# ModuleCarrier-RAK811-v1_0_0.net
KiCad netlist of a schematic drawn in EAGLE
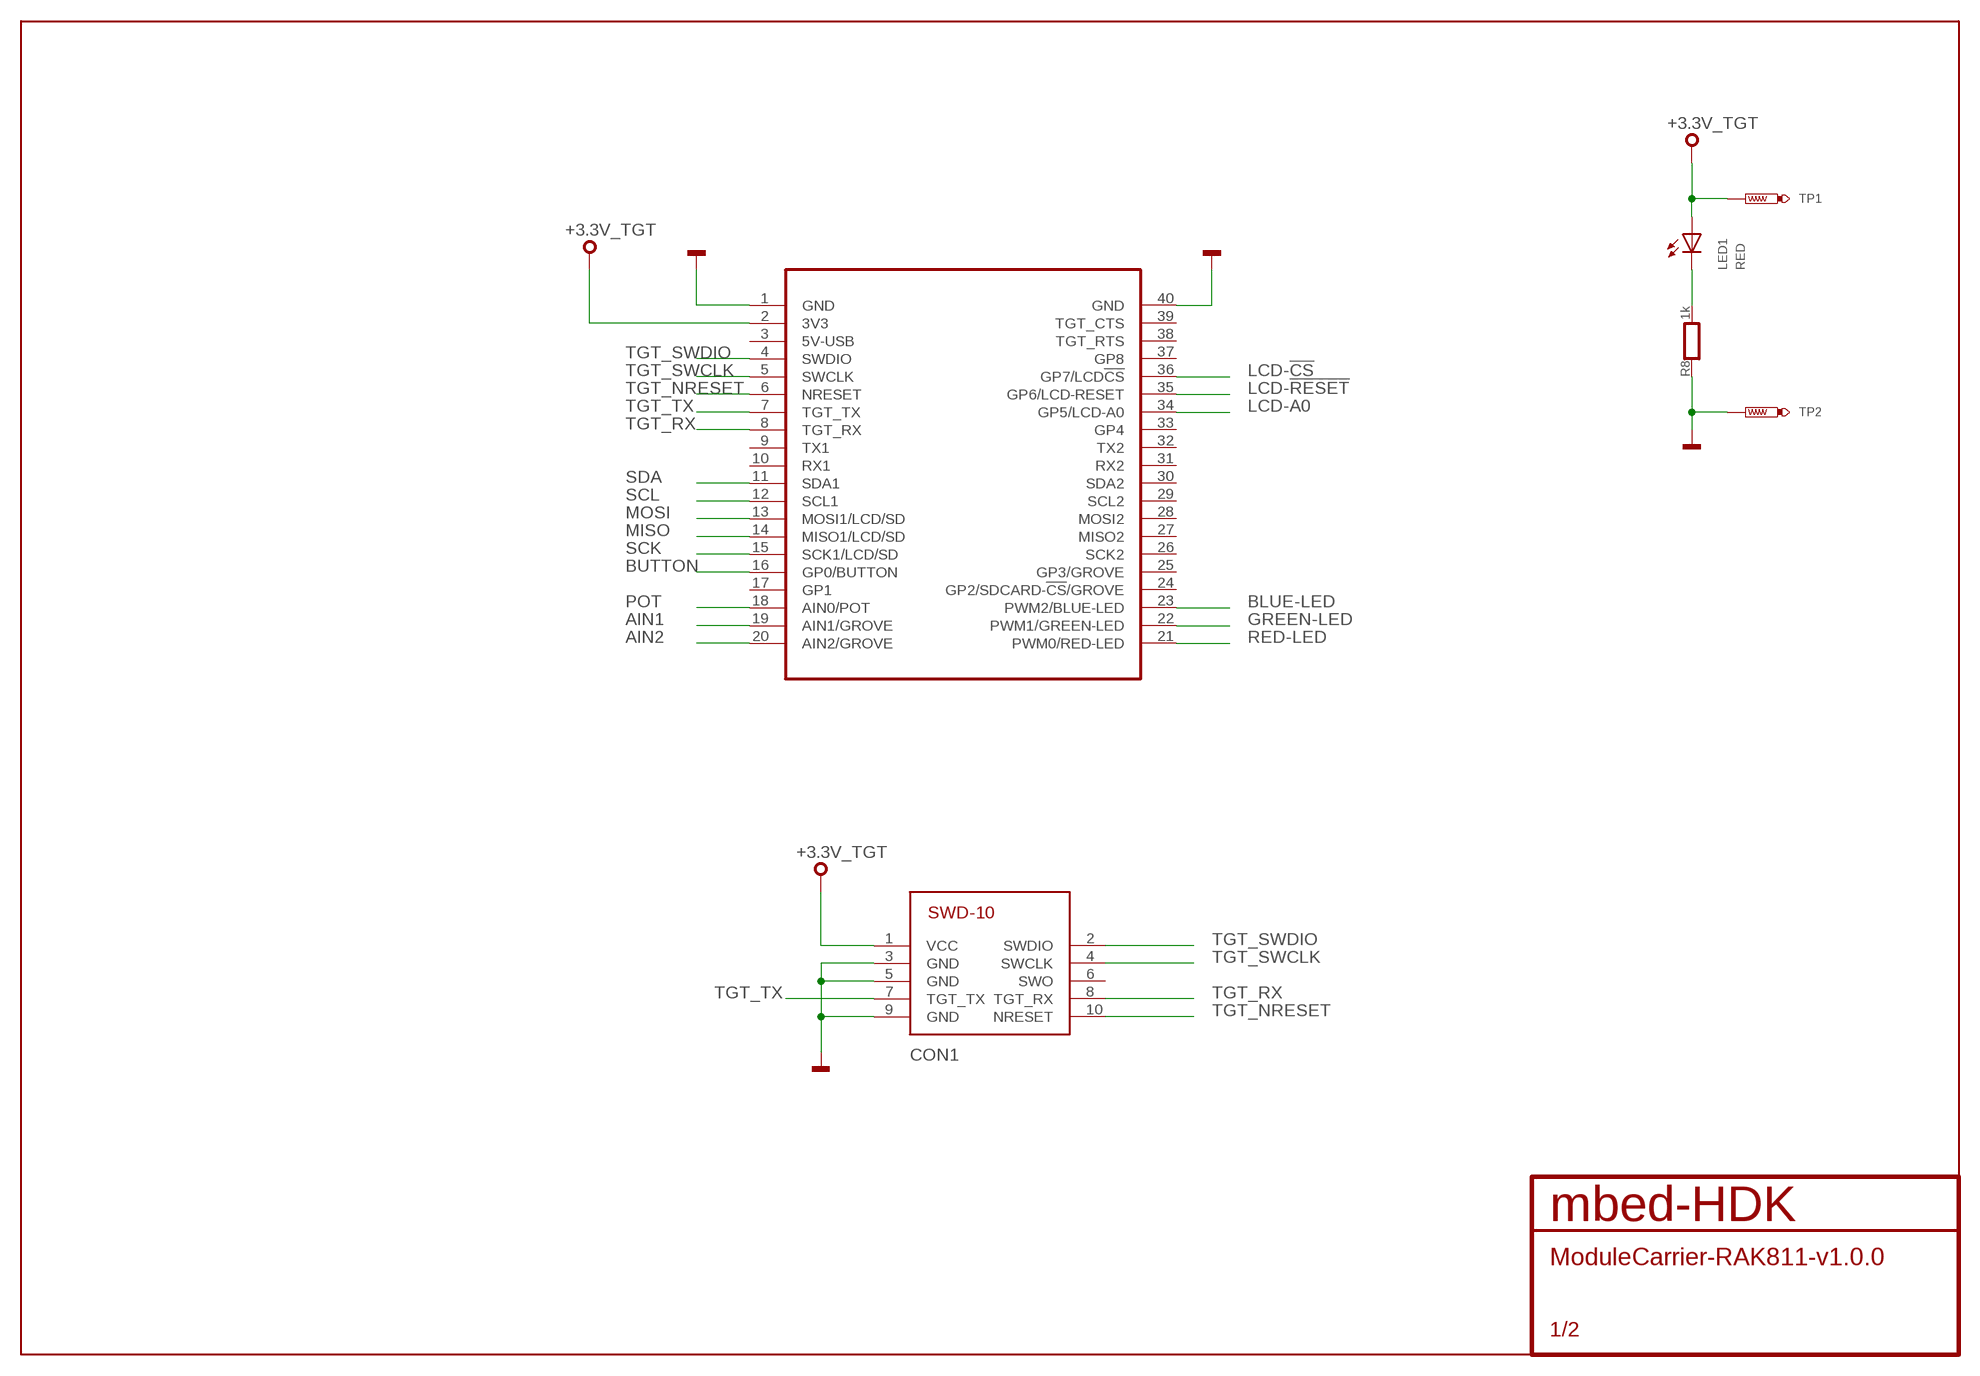
[diagram p0: schematic, sheet 1]
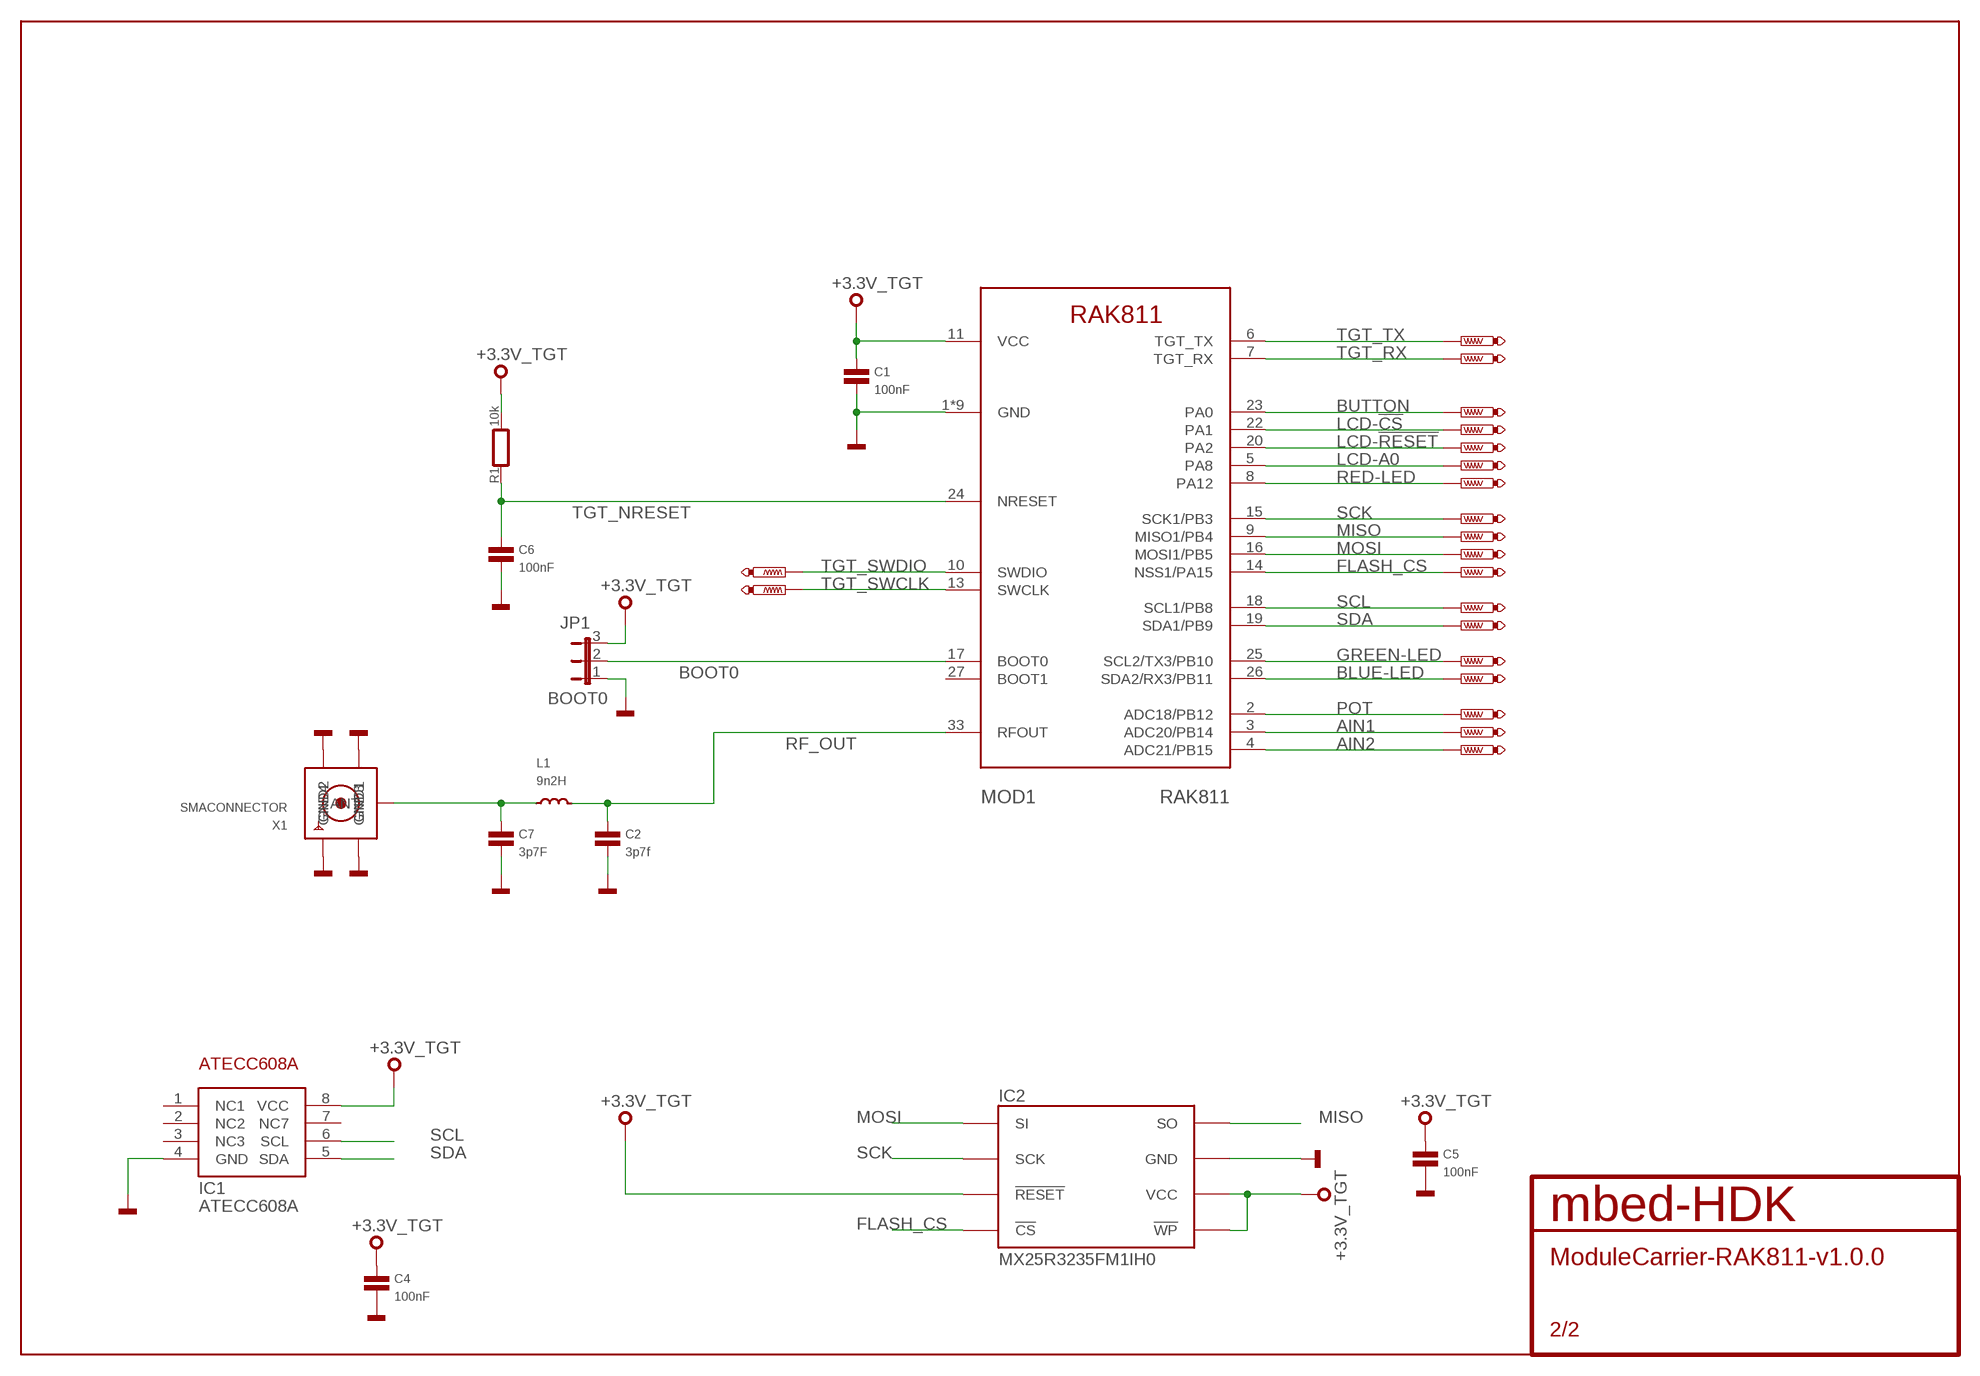
[diagram p1: schematic, sheet 2]

(export (version "E")
  (design (tool "Eeschema 10.0.6"))
  (components
    (comp (ref "C1")
      (value "100nF")
      (footprint "eagle-import:0603")
      (libsource (lib "eagle-import") (part "CAPACITOR0603"))
    )
    (comp (ref "C2")
      (value "3p7f")
      (footprint "eagle-import:0603")
      (libsource (lib "eagle-import") (part "CAPACITOR0603"))
    )
    (comp (ref "C4")
      (value "100nF")
      (footprint "eagle-import:0603")
      (libsource (lib "eagle-import") (part "CAPACITOR0603"))
    )
    (comp (ref "C5")
      (value "100nF")
      (footprint "eagle-import:0603")
      (libsource (lib "eagle-import") (part "CAPACITOR0603"))
    )
    (comp (ref "C6")
      (value "100nF")
      (footprint "eagle-import:0603")
      (libsource (lib "eagle-import") (part "CAPACITOR0603"))
    )
    (comp (ref "C7")
      (value "3p7F")
      (footprint "eagle-import:0603")
      (libsource (lib "eagle-import") (part "CAPACITOR0603"))
    )
    (comp (ref "IC1")
      (value "ATECC608A")
      (footprint "eagle-import:SO8")
      (libsource (lib "eagle-import") (part "ATECC608A"))
    )
    (comp (ref "IC2")
      (value "MX25R3235FM1IH0")
      (footprint "eagle-import:SO8")
      (fields (field (name "MF") "Macronix"))
      (libsource (lib "eagle-import") (part "MX25R3235FM1IH0"))
    )
    (comp (ref "JP1")
      (value "BOOT0")
      (footprint "eagle-import:JP2")
      (libsource (lib "eagle-import") (part "JP2E"))
    )
    (comp (ref "L1")
      (value "9n2H")
      (footprint "eagle-import:0603")
      (libsource (lib "eagle-import") (part "INDUCTOR0603"))
    )
    (comp (ref "MOD1")
      (value "RAK811")
      (footprint "eagle-import:RAK811")
      (libsource (lib "eagle-import") (part "RAK811"))
    )
    (comp (ref "R1")
      (value "10k")
      (footprint "eagle-import:0603")
      (libsource (lib "eagle-import") (part "RESISTOR0603"))
    )
    (comp (ref "TP3")
      (value "PTR1TP10R")
      (footprint "eagle-import:TP10R")
      (libsource (lib "eagle-import") (part "PTR1TP10R"))
    )
    (comp (ref "TP4")
      (value "PTR1TP10R")
      (footprint "eagle-import:TP10R")
      (libsource (lib "eagle-import") (part "PTR1TP10R"))
    )
    (comp (ref "TP5")
      (value "PTR1TP10R")
      (footprint "eagle-import:TP10R")
      (libsource (lib "eagle-import") (part "PTR1TP10R"))
    )
    (comp (ref "TP6")
      (value "PTR1TP10R")
      (footprint "eagle-import:TP10R")
      (libsource (lib "eagle-import") (part "PTR1TP10R"))
    )
    (comp (ref "TP7")
      (value "PTR1TP10R")
      (footprint "eagle-import:TP10R")
      (libsource (lib "eagle-import") (part "PTR1TP10R"))
    )
    (comp (ref "TP8")
      (value "PTR1TP10R")
      (footprint "eagle-import:TP10R")
      (libsource (lib "eagle-import") (part "PTR1TP10R"))
    )
    (comp (ref "TP9")
      (value "PTR1TP10R")
      (footprint "eagle-import:TP10R")
      (libsource (lib "eagle-import") (part "PTR1TP10R"))
    )
    (comp (ref "TP10")
      (value "PTR1TP10R")
      (footprint "eagle-import:TP10R")
      (libsource (lib "eagle-import") (part "PTR1TP10R"))
    )
    (comp (ref "TP11")
      (value "PTR1TP10R")
      (footprint "eagle-import:TP10R")
      (libsource (lib "eagle-import") (part "PTR1TP10R"))
    )
    (comp (ref "TP12")
      (value "PTR1TP10R")
      (footprint "eagle-import:TP10R")
      (libsource (lib "eagle-import") (part "PTR1TP10R"))
    )
    (comp (ref "TP13")
      (value "PTR1TP10R")
      (footprint "eagle-import:TP10R")
      (libsource (lib "eagle-import") (part "PTR1TP10R"))
    )
    (comp (ref "TP14")
      (value "PTR1TP10R")
      (footprint "eagle-import:TP10R")
      (libsource (lib "eagle-import") (part "PTR1TP10R"))
    )
    (comp (ref "TP15")
      (value "PTR1TP10R")
      (footprint "eagle-import:TP10R")
      (libsource (lib "eagle-import") (part "PTR1TP10R"))
    )
    (comp (ref "TP16")
      (value "PTR1TP10R")
      (footprint "eagle-import:TP10R")
      (libsource (lib "eagle-import") (part "PTR1TP10R"))
    )
    (comp (ref "TP17")
      (value "PTR1TP10R")
      (footprint "eagle-import:TP10R")
      (libsource (lib "eagle-import") (part "PTR1TP10R"))
    )
    (comp (ref "TP18")
      (value "PTR1TP10R")
      (footprint "eagle-import:TP10R")
      (libsource (lib "eagle-import") (part "PTR1TP10R"))
    )
    (comp (ref "TP19")
      (value "PTR1TP10R")
      (footprint "eagle-import:TP10R")
      (libsource (lib "eagle-import") (part "PTR1TP10R"))
    )
    (comp (ref "TP20")
      (value "PTR1TP10R")
      (footprint "eagle-import:TP10R")
      (libsource (lib "eagle-import") (part "PTR1TP10R"))
    )
    (comp (ref "TP21")
      (value "PTR1TP10R")
      (footprint "eagle-import:TP10R")
      (libsource (lib "eagle-import") (part "PTR1TP10R"))
    )
    (comp (ref "TP22")
      (value "PTR1TP10R")
      (footprint "eagle-import:TP10R")
      (libsource (lib "eagle-import") (part "PTR1TP10R"))
    )
    (comp (ref "X1")
      (value "SMACONNECTOR")
      (footprint "eagle-import:SMA90_DIP")
      (fields (field (name "MF") "LPRS") (field (name "MP") "SMA CONNECTOR"))
      (libsource (lib "eagle-import") (part "SMACONNECTOR"))
    )
    (comp (ref "CON1")
      (value "SWD-10/TC2050_SMD")
      (footprint "eagle-import:FTSH-105-02")
      (libsource (lib "eagle-import") (part "SWD-10/TC2050_SMD"))
    )
    (comp (ref "LED1")
      (value "RED")
      (footprint "eagle-import:CHIPLED_0603")
      (fields (field (name "MF") "Wurth Electronics Inc"))
      (libsource (lib "eagle-import") (part "SMD_LED0603"))
    )
    (comp (ref "MOD2")
      (value "MODULE_DAUGHTER")
      (footprint "eagle-import:MODULE_DAUGHTER")
      (libsource (lib "eagle-import") (part "MODULE_DAUGHTER"))
    )
    (comp (ref "R8")
      (value "1k")
      (footprint "eagle-import:0603")
      (libsource (lib "eagle-import") (part "RESISTOR0603"))
    )
    (comp (ref "TP1")
      (value "TEST-POINT-50R-PTH")
      (footprint "eagle-import:TP50-PTH")
      (libsource (lib "eagle-import") (part "TEST-POINT-50R-PTH"))
    )
    (comp (ref "TP2")
      (value "TEST-POINT-50R-PTH")
      (footprint "eagle-import:TP50-PTH")
      (libsource (lib "eagle-import") (part "TEST-POINT-50R-PTH"))
    )
  )
  (nets
    (net (code "1") (name "+3.3V_TGT") (class "Default")
      (node (ref "C1") (pin "1") (pinfunction "P$1_1") (pintype "passive"))
      (node (ref "C4") (pin "1") (pinfunction "P$1_1") (pintype "passive"))
      (node (ref "C5") (pin "1") (pinfunction "P$1_1") (pintype "passive"))
      (node (ref "CON1") (pin "1") (pinfunction "VCC_1") (pintype "bidirectional"))
      (node (ref "IC1") (pin "8") (pinfunction "VCC_8") (pintype "bidirectional"))
      (node (ref "IC2") (pin "3") (pinfunction "~{WP}_3") (pintype "bidirectional"))
      (node (ref "IC2") (pin "7") (pinfunction "~{RESET}_7") (pintype "bidirectional"))
      (node (ref "IC2") (pin "8") (pinfunction "VCC_8") (pintype "bidirectional"))
      (node (ref "JP1") (pin "3") (pinfunction "3_3") (pintype "passive"))
      (node (ref "LED1") (pin "A") (pinfunction "A_A") (pintype "passive"))
      (node (ref "MOD1") (pin "11") (pinfunction "VCC_11") (pintype "bidirectional"))
      (node (ref "MOD2") (pin "2") (pinfunction "3V3_2") (pintype "bidirectional"))
      (node (ref "R1") (pin "2") (pinfunction "P$2_2") (pintype "passive"))
      (node (ref "TP1") (pin "TP") (pinfunction "TP_TP") (pintype "input"))
    )
    (net (code "2") (name "AIN1") (class "Default")
      (node (ref "MOD1") (pin "3") (pinfunction "ADC20/PB14_3") (pintype "bidirectional"))
      (node (ref "MOD2") (pin "19") (pinfunction "AIN1/GROVE_19") (pintype "bidirectional"))
      (node (ref "TP13") (pin "TP") (pinfunction "TP_TP") (pintype "input"))
    )
    (net (code "3") (name "AIN2") (class "Default")
      (node (ref "MOD1") (pin "4") (pinfunction "ADC21/PB15_4") (pintype "bidirectional"))
      (node (ref "MOD2") (pin "20") (pinfunction "AIN2/GROVE_20") (pintype "bidirectional"))
      (node (ref "TP12") (pin "TP") (pinfunction "TP_TP") (pintype "input"))
    )
    (net (code "4") (name "BLUE-LED") (class "Default")
      (node (ref "MOD1") (pin "26") (pinfunction "SDA2/RX3/PB11_26") (pintype "bidirectional"))
      (node (ref "MOD2") (pin "23") (pinfunction "PWM2/BLUE-LED_23") (pintype "bidirectional"))
      (node (ref "TP15") (pin "TP") (pinfunction "TP_TP") (pintype "input"))
    )
    (net (code "5") (name "BOOT0") (class "Default")
      (node (ref "JP1") (pin "2") (pinfunction "2_2") (pintype "passive"))
      (node (ref "MOD1") (pin "17") (pinfunction "BOOT0_17") (pintype "bidirectional"))
    )
    (net (code "6") (name "BUTTON") (class "Default")
      (node (ref "MOD1") (pin "23") (pinfunction "PA0_23") (pintype "bidirectional"))
      (node (ref "MOD2") (pin "16") (pinfunction "GP0/BUTTON_16") (pintype "bidirectional"))
      (node (ref "TP7") (pin "TP") (pinfunction "TP_TP") (pintype "input"))
    )
    (net (code "7") (name "FLASH_CS") (class "Default")
      (node (ref "IC2") (pin "1") (pinfunction "~{CS}_1") (pintype "bidirectional"))
      (node (ref "MOD1") (pin "14") (pinfunction "NSS1/PA15_14") (pintype "bidirectional"))
      (node (ref "TP19") (pin "TP") (pinfunction "TP_TP") (pintype "input"))
    )
    (net (code "8") (name "GND") (class "Default")
      (node (ref "C1") (pin "2") (pinfunction "P$2_2") (pintype "passive"))
      (node (ref "C2") (pin "2") (pinfunction "P$2_2") (pintype "passive"))
      (node (ref "C4") (pin "2") (pinfunction "P$2_2") (pintype "passive"))
      (node (ref "C5") (pin "2") (pinfunction "P$2_2") (pintype "passive"))
      (node (ref "C6") (pin "2") (pinfunction "P$2_2") (pintype "passive"))
      (node (ref "C7") (pin "2") (pinfunction "P$2_2") (pintype "passive"))
      (node (ref "CON1") (pin "3") (pinfunction "GND_3") (pintype "bidirectional"))
      (node (ref "CON1") (pin "5") (pinfunction "GND_5") (pintype "bidirectional"))
      (node (ref "CON1") (pin "9") (pinfunction "GND_9") (pintype "bidirectional"))
      (node (ref "IC1") (pin "4") (pinfunction "GND_4") (pintype "bidirectional"))
      (node (ref "IC2") (pin "4") (pinfunction "GND_4") (pintype "bidirectional"))
      (node (ref "JP1") (pin "1") (pinfunction "1_1") (pintype "passive"))
      (node (ref "MOD1") (pin "1") (pinfunction "GND_1") (pintype "bidirectional"))
      (node (ref "MOD1") (pin "12") (pinfunction "GND_12") (pintype "bidirectional"))
      (node (ref "MOD1") (pin "21") (pinfunction "GND_21") (pintype "bidirectional"))
      (node (ref "MOD1") (pin "28") (pinfunction "GND_28") (pintype "bidirectional"))
      (node (ref "MOD1") (pin "29") (pinfunction "GND_29") (pintype "bidirectional"))
      (node (ref "MOD1") (pin "30") (pinfunction "GND_30") (pintype "bidirectional"))
      (node (ref "MOD1") (pin "31") (pinfunction "GND_31") (pintype "bidirectional"))
      (node (ref "MOD1") (pin "32") (pinfunction "GND_32") (pintype "bidirectional"))
      (node (ref "MOD1") (pin "34") (pinfunction "GND_34") (pintype "bidirectional"))
      (node (ref "MOD2") (pin "1") (pinfunction "GND_1") (pintype "bidirectional"))
      (node (ref "MOD2") (pin "40") (pinfunction "GND_40") (pintype "bidirectional"))
      (node (ref "R8") (pin "1") (pinfunction "P$1_1") (pintype "passive"))
      (node (ref "TP2") (pin "TP") (pinfunction "TP_TP") (pintype "input"))
      (node (ref "X1") (pin "GND1") (pinfunction "GND1_GND1") (pintype "power_in"))
      (node (ref "X1") (pin "GND2") (pinfunction "GND2_GND2") (pintype "power_in"))
      (node (ref "X1") (pin "GND3") (pinfunction "GND3_GND3") (pintype "power_in"))
      (node (ref "X1") (pin "GND4") (pinfunction "GND4_GND4") (pintype "power_in"))
    )
    (net (code "9") (name "GREEN-LED") (class "Default")
      (node (ref "MOD1") (pin "25") (pinfunction "SCL2/TX3/PB10_25") (pintype "bidirectional"))
      (node (ref "MOD2") (pin "22") (pinfunction "PWM1/GREEN-LED_22") (pintype "bidirectional"))
      (node (ref "TP16") (pin "TP") (pinfunction "TP_TP") (pintype "input"))
    )
    (net (code "10") (name "LCD-A0") (class "Default")
      (node (ref "MOD1") (pin "5") (pinfunction "PA8_5") (pintype "bidirectional"))
      (node (ref "MOD2") (pin "34") (pinfunction "GP5/LCD-A0_34") (pintype "bidirectional"))
      (node (ref "TP10") (pin "TP") (pinfunction "TP_TP") (pintype "input"))
    )
    (net (code "11") (name "LCD-~{CS}") (class "Default")
      (node (ref "MOD1") (pin "22") (pinfunction "PA1_22") (pintype "bidirectional"))
      (node (ref "MOD2") (pin "36") (pinfunction "GP7/LCD~{CS}_36") (pintype "bidirectional"))
      (node (ref "TP8") (pin "TP") (pinfunction "TP_TP") (pintype "input"))
    )
    (net (code "12") (name "LCD-~{RESET}") (class "Default")
      (node (ref "MOD1") (pin "20") (pinfunction "PA2_20") (pintype "bidirectional"))
      (node (ref "MOD2") (pin "35") (pinfunction "GP6/LCD-RESET_35") (pintype "bidirectional"))
      (node (ref "TP9") (pin "TP") (pinfunction "TP_TP") (pintype "input"))
    )
    (net (code "13") (name "MISO") (class "Default")
      (node (ref "IC2") (pin "2") (pinfunction "SO_2") (pintype "bidirectional"))
      (node (ref "MOD1") (pin "9") (pinfunction "MISO1/PB4_9") (pintype "bidirectional"))
      (node (ref "MOD2") (pin "14") (pinfunction "MISO1/LCD/SD_14") (pintype "bidirectional"))
      (node (ref "TP21") (pin "TP") (pinfunction "TP_TP") (pintype "input"))
    )
    (net (code "14") (name "MOSI") (class "Default")
      (node (ref "IC2") (pin "5") (pinfunction "SI_5") (pintype "bidirectional"))
      (node (ref "MOD1") (pin "16") (pinfunction "MOSI1/PB5_16") (pintype "bidirectional"))
      (node (ref "MOD2") (pin "13") (pinfunction "MOSI1/LCD/SD_13") (pintype "bidirectional"))
      (node (ref "TP20") (pin "TP") (pinfunction "TP_TP") (pintype "input"))
    )
    (net (code "15") (name "Net-(C7-P$1)") (class "Default")
      (node (ref "C7") (pin "1") (pinfunction "P$1_1") (pintype "passive"))
      (node (ref "L1") (pin "1") (pinfunction "P$1_1") (pintype "bidirectional"))
      (node (ref "X1") (pin "ANTENNA") (pinfunction "ANT_ANTENNA") (pintype "bidirectional"))
    )
    (net (code "16") (name "Net-(R8-P$2)") (class "Default")
      (node (ref "LED1") (pin "C") (pinfunction "C_C") (pintype "passive"))
      (node (ref "R8") (pin "2") (pinfunction "P$2_2") (pintype "passive"))
    )
    (net (code "17") (name "POT") (class "Default")
      (node (ref "MOD1") (pin "2") (pinfunction "ADC18/PB12_2") (pintype "bidirectional"))
      (node (ref "MOD2") (pin "18") (pinfunction "AIN0/POT_18") (pintype "bidirectional"))
      (node (ref "TP14") (pin "TP") (pinfunction "TP_TP") (pintype "input"))
    )
    (net (code "18") (name "RED-LED") (class "Default")
      (node (ref "MOD1") (pin "8") (pinfunction "PA12_8") (pintype "bidirectional"))
      (node (ref "MOD2") (pin "21") (pinfunction "PWM0/RED-LED_21") (pintype "bidirectional"))
      (node (ref "TP11") (pin "TP") (pinfunction "TP_TP") (pintype "input"))
    )
    (net (code "19") (name "RF_OUT") (class "Default")
      (node (ref "C2") (pin "1") (pinfunction "P$1_1") (pintype "passive"))
      (node (ref "L1") (pin "2") (pinfunction "P$2_2") (pintype "bidirectional"))
      (node (ref "MOD1") (pin "33") (pinfunction "RFOUT_33") (pintype "bidirectional"))
    )
    (net (code "20") (name "SCK") (class "Default")
      (node (ref "IC2") (pin "6") (pinfunction "SCK_6") (pintype "bidirectional"))
      (node (ref "MOD1") (pin "15") (pinfunction "SCK1/PB3_15") (pintype "bidirectional"))
      (node (ref "MOD2") (pin "15") (pinfunction "SCK1/LCD/SD_15") (pintype "bidirectional"))
      (node (ref "TP22") (pin "TP") (pinfunction "TP_TP") (pintype "input"))
    )
    (net (code "21") (name "SCL") (class "Default")
      (node (ref "IC1") (pin "6") (pinfunction "SCL_6") (pintype "bidirectional"))
      (node (ref "MOD1") (pin "18") (pinfunction "SCL1/PB8_18") (pintype "bidirectional"))
      (node (ref "MOD2") (pin "12") (pinfunction "SCL1_12") (pintype "bidirectional"))
      (node (ref "TP18") (pin "TP") (pinfunction "TP_TP") (pintype "input"))
    )
    (net (code "22") (name "SDA") (class "Default")
      (node (ref "IC1") (pin "5") (pinfunction "SDA_5") (pintype "bidirectional"))
      (node (ref "MOD1") (pin "19") (pinfunction "SDA1/PB9_19") (pintype "bidirectional"))
      (node (ref "MOD2") (pin "11") (pinfunction "SDA1_11") (pintype "bidirectional"))
      (node (ref "TP17") (pin "TP") (pinfunction "TP_TP") (pintype "input"))
    )
    (net (code "23") (name "TGT_NRESET") (class "Default")
      (node (ref "C6") (pin "1") (pinfunction "P$1_1") (pintype "passive"))
      (node (ref "CON1") (pin "10") (pinfunction "NRESET_10") (pintype "bidirectional"))
      (node (ref "MOD1") (pin "24") (pinfunction "NRESET_24") (pintype "bidirectional"))
      (node (ref "MOD2") (pin "6") (pinfunction "NRESET_6") (pintype "bidirectional"))
      (node (ref "R1") (pin "1") (pinfunction "P$1_1") (pintype "passive"))
    )
    (net (code "24") (name "TGT_RX") (class "Default")
      (node (ref "CON1") (pin "8") (pinfunction "TGT_RX_8") (pintype "bidirectional"))
      (node (ref "MOD1") (pin "7") (pinfunction "TGT_RX_7") (pintype "bidirectional"))
      (node (ref "MOD2") (pin "8") (pinfunction "TGT_RX_8") (pintype "bidirectional"))
      (node (ref "TP6") (pin "TP") (pinfunction "TP_TP") (pintype "input"))
    )
    (net (code "25") (name "TGT_SWCLK") (class "Default")
      (node (ref "CON1") (pin "4") (pinfunction "SWCLK_4") (pintype "bidirectional"))
      (node (ref "MOD1") (pin "13") (pinfunction "SWCLK_13") (pintype "bidirectional"))
      (node (ref "MOD2") (pin "5") (pinfunction "SWCLK_5") (pintype "bidirectional"))
      (node (ref "TP4") (pin "TP") (pinfunction "TP_TP") (pintype "input"))
    )
    (net (code "26") (name "TGT_SWDIO") (class "Default")
      (node (ref "CON1") (pin "2") (pinfunction "SWDIO_2") (pintype "bidirectional"))
      (node (ref "MOD1") (pin "10") (pinfunction "SWDIO_10") (pintype "bidirectional"))
      (node (ref "MOD2") (pin "4") (pinfunction "SWDIO_4") (pintype "bidirectional"))
      (node (ref "TP3") (pin "TP") (pinfunction "TP_TP") (pintype "input"))
    )
    (net (code "27") (name "TGT_TX") (class "Default")
      (node (ref "CON1") (pin "7") (pinfunction "TGT_TX_7") (pintype "bidirectional"))
      (node (ref "MOD1") (pin "6") (pinfunction "TGT_TX_6") (pintype "bidirectional"))
      (node (ref "MOD2") (pin "7") (pinfunction "TGT_TX_7") (pintype "bidirectional"))
      (node (ref "TP5") (pin "TP") (pinfunction "TP_TP") (pintype "input"))
    )
    (net (code "28") (name "unconnected-(CON1-SWO-Pad6)") (class "Default")
      (node (ref "CON1") (pin "6") (pinfunction "SWO_6") (pintype "bidirectional"))
    )
    (net (code "29") (name "unconnected-(IC1-NC1-Pad1)") (class "Default")
      (node (ref "IC1") (pin "1") (pinfunction "NC1_1") (pintype "bidirectional"))
    )
    (net (code "30") (name "unconnected-(IC1-NC2-Pad2)") (class "Default")
      (node (ref "IC1") (pin "2") (pinfunction "NC2_2") (pintype "bidirectional"))
    )
    (net (code "31") (name "unconnected-(IC1-NC3-Pad3)") (class "Default")
      (node (ref "IC1") (pin "3") (pinfunction "NC3_3") (pintype "bidirectional"))
    )
    (net (code "32") (name "unconnected-(IC1-NC7-Pad7)") (class "Default")
      (node (ref "IC1") (pin "7") (pinfunction "NC7_7") (pintype "bidirectional"))
    )
    (net (code "33") (name "unconnected-(MOD1-BOOT1-Pad27)") (class "Default")
      (node (ref "MOD1") (pin "27") (pinfunction "BOOT1_27") (pintype "bidirectional"))
    )
    (net (code "34") (name "unconnected-(MOD2-5V-USB-Pad3)") (class "Default")
      (node (ref "MOD2") (pin "3") (pinfunction "5V-USB_3") (pintype "bidirectional"))
    )
    (net (code "35") (name "unconnected-(MOD2-GP1-Pad17)") (class "Default")
      (node (ref "MOD2") (pin "17") (pinfunction "GP1_17") (pintype "bidirectional"))
    )
    (net (code "36") (name "unconnected-(MOD2-GP2{slash}SDCARD-~{CS}{slash}GROVE-Pad24)") (class "Default")
      (node (ref "MOD2") (pin "24") (pinfunction "GP2/SDCARD-~{CS}/GROVE_24") (pintype "bidirectional"))
    )
    (net (code "37") (name "unconnected-(MOD2-GP3{slash}GROVE-Pad25)") (class "Default")
      (node (ref "MOD2") (pin "25") (pinfunction "GP3/GROVE_25") (pintype "bidirectional"))
    )
    (net (code "38") (name "unconnected-(MOD2-GP4-Pad33)") (class "Default")
      (node (ref "MOD2") (pin "33") (pinfunction "GP4_33") (pintype "bidirectional"))
    )
    (net (code "39") (name "unconnected-(MOD2-GP8-Pad37)") (class "Default")
      (node (ref "MOD2") (pin "37") (pinfunction "GP8_37") (pintype "bidirectional"))
    )
    (net (code "40") (name "unconnected-(MOD2-MISO2-Pad27)") (class "Default")
      (node (ref "MOD2") (pin "27") (pinfunction "MISO2_27") (pintype "bidirectional"))
    )
    (net (code "41") (name "unconnected-(MOD2-MOSI2-Pad28)") (class "Default")
      (node (ref "MOD2") (pin "28") (pinfunction "MOSI2_28") (pintype "bidirectional"))
    )
    (net (code "42") (name "unconnected-(MOD2-RX1-Pad10)") (class "Default")
      (node (ref "MOD2") (pin "10") (pinfunction "RX1_10") (pintype "bidirectional"))
    )
    (net (code "43") (name "unconnected-(MOD2-RX2-Pad31)") (class "Default")
      (node (ref "MOD2") (pin "31") (pinfunction "RX2_31") (pintype "bidirectional"))
    )
    (net (code "44") (name "unconnected-(MOD2-SCK2-Pad26)") (class "Default")
      (node (ref "MOD2") (pin "26") (pinfunction "SCK2_26") (pintype "bidirectional"))
    )
    (net (code "45") (name "unconnected-(MOD2-SCL2-Pad29)") (class "Default")
      (node (ref "MOD2") (pin "29") (pinfunction "SCL2_29") (pintype "bidirectional"))
    )
    (net (code "46") (name "unconnected-(MOD2-SDA2-Pad30)") (class "Default")
      (node (ref "MOD2") (pin "30") (pinfunction "SDA2_30") (pintype "bidirectional"))
    )
    (net (code "47") (name "unconnected-(MOD2-TGT_CTS-Pad39)") (class "Default")
      (node (ref "MOD2") (pin "39") (pinfunction "TGT_CTS_39") (pintype "bidirectional"))
    )
    (net (code "48") (name "unconnected-(MOD2-TGT_RTS-Pad38)") (class "Default")
      (node (ref "MOD2") (pin "38") (pinfunction "TGT_RTS_38") (pintype "bidirectional"))
    )
    (net (code "49") (name "unconnected-(MOD2-TX1-Pad9)") (class "Default")
      (node (ref "MOD2") (pin "9") (pinfunction "TX1_9") (pintype "bidirectional"))
    )
    (net (code "50") (name "unconnected-(MOD2-TX2-Pad32)") (class "Default")
      (node (ref "MOD2") (pin "32") (pinfunction "TX2_32") (pintype "bidirectional"))
    )
  )
)
